# CANBUS_Pendant.net
KiCad netlist of a schematic drawn in Altium Designer
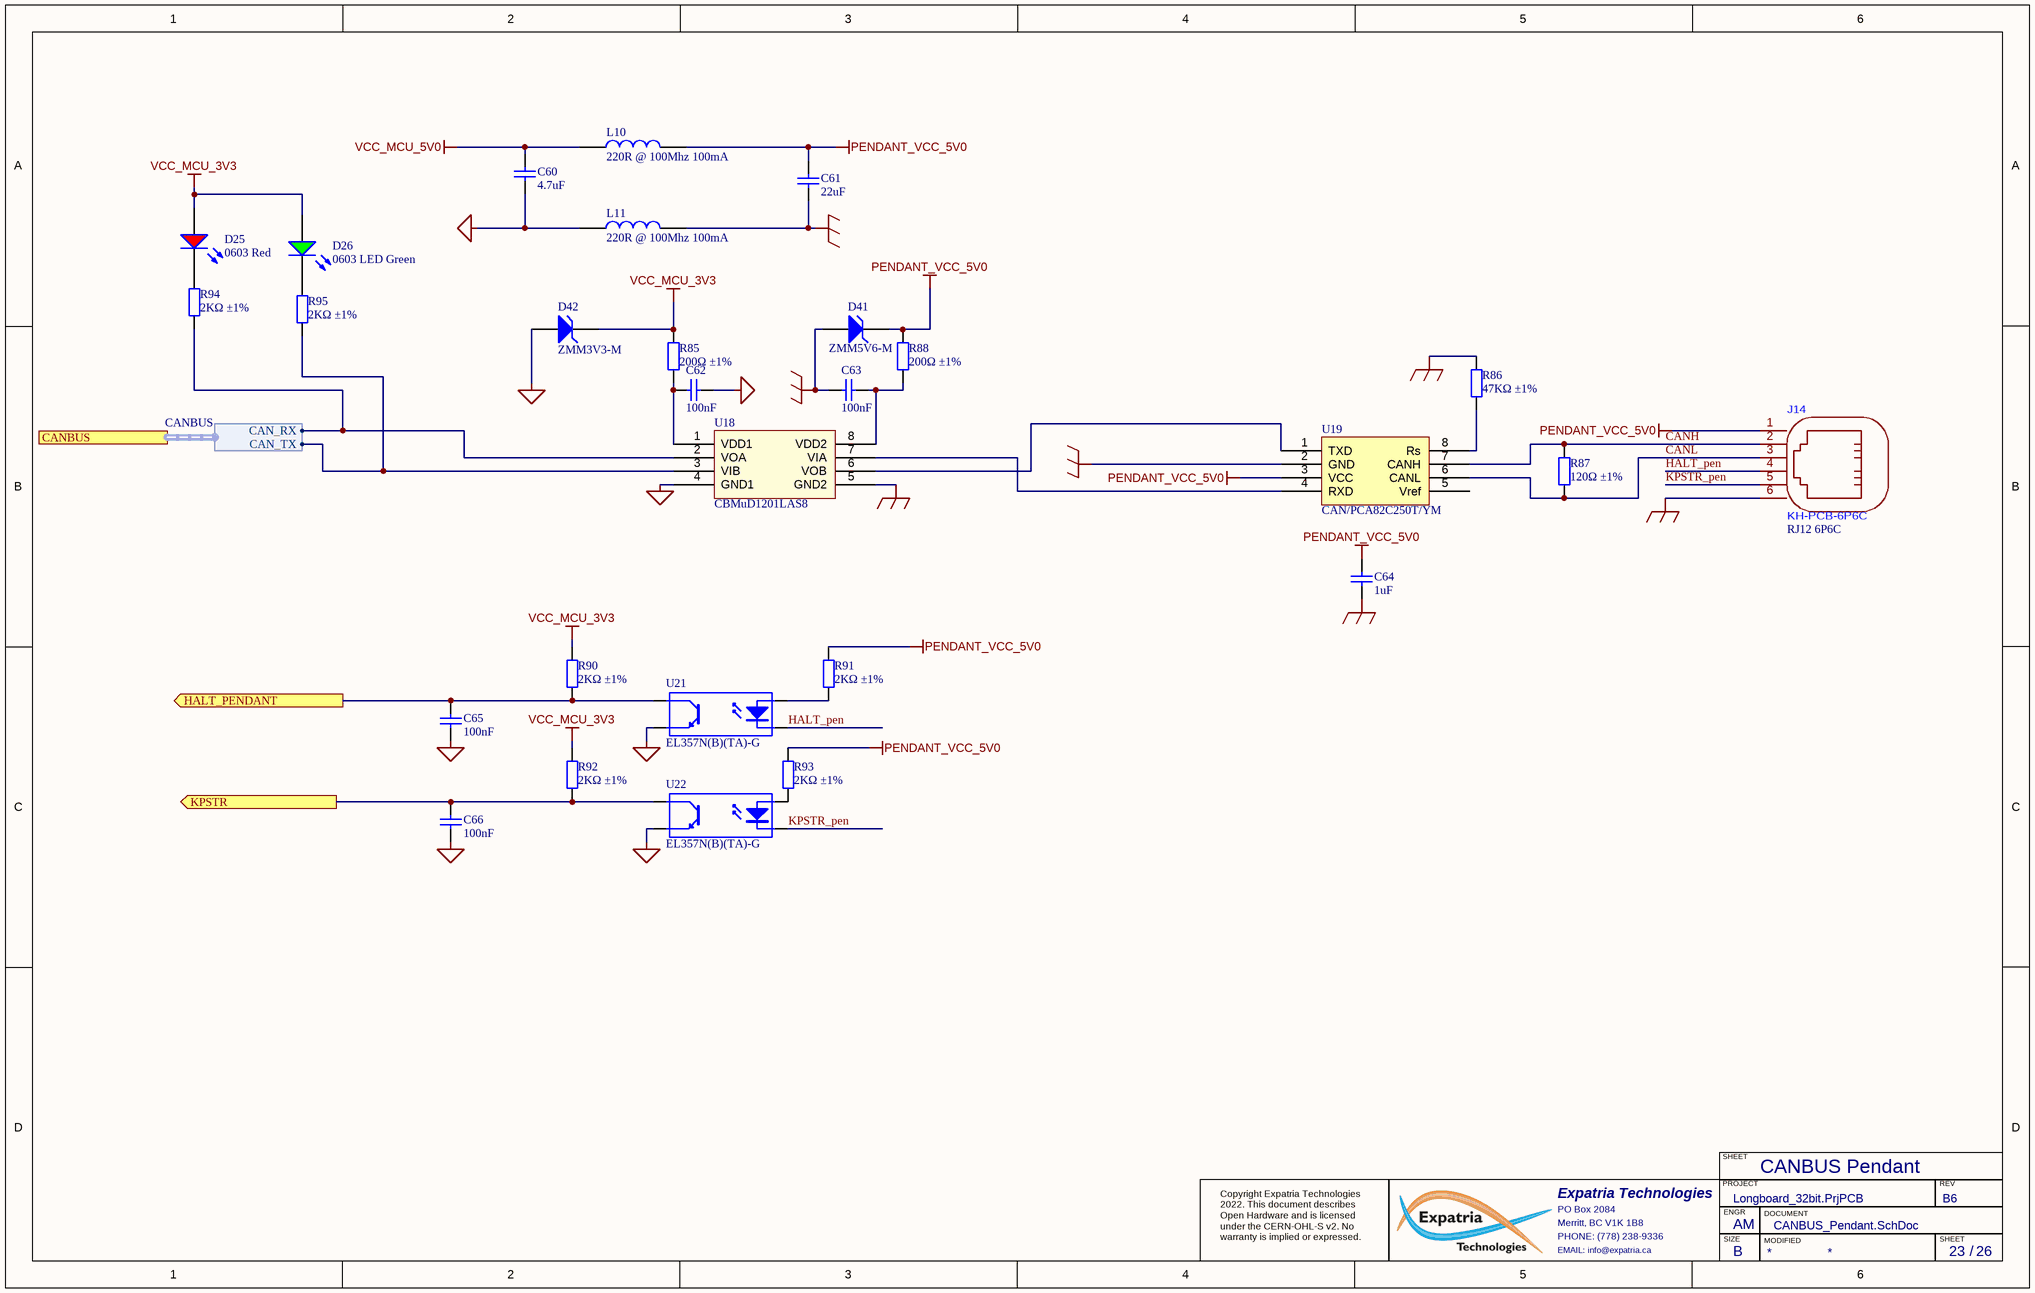
[diagram p0: CANBUS_Pendant.SchDoc]

(export (version "E")
  (design (tool "Eeschema 10.0.6"))
  (components
    (comp (ref "C60")
      (value "4.7uF")
      (footprint "0805_C")
      (description "Chip capacitors")
      (fields
        (field (name "MANUFACTURER") "Samsung Electro-Mechanics")
        (field (name "PARTNUMBER") "CL21A475KAQNNNE")
      )
      (libsource (lib "Cap") (part "0805 4.7uF (475) 10% 25V"))
    )
    (comp (ref "C61")
      (value "22uF")
      (footprint "0805_C")
      (description "25V 22uF X5R ±20% 0805 Multilayer Ceramic Capacitors MLCC - SMD/SMT ROHS")
      (fields (field (name "MANUFACTURER") "Samsung Electro-Mechanics") (field (name "TOLERANCE") "20%"))
      (libsource (lib "Sienci_Labs") (part "0805 22uF (226) 20% 25V"))
    )
    (comp (ref "C62")
      (value "100nF")
      (footprint "0402_C")
      (description "16V 100nF X7R ±10% 0402 Multilayer Ceramic Capacitors MLCC - SMD/SMT ROHS")
      (fields (field (name "MANUFACTURER") "Samsung Electro-Mechanics") (field (name "TOLERANCE") "10%"))
      (libsource (lib "Sienci_Labs") (part "0402 100nF (104) 10% 16V"))
    )
    (comp (ref "C63")
      (value "100nF")
      (footprint "0402_C")
      (description "16V 100nF X7R ±10% 0402 Multilayer Ceramic Capacitors MLCC - SMD/SMT ROHS")
      (fields (field (name "MANUFACTURER") "Samsung Electro-Mechanics") (field (name "TOLERANCE") "10%"))
      (libsource (lib "Sienci_Labs") (part "0402 100nF (104) 10% 16V"))
    )
    (comp (ref "C64")
      (value "1uF")
      (footprint "0603_C")
      (description "Chip capacitors")
      (fields
        (field (name "MANUFACTURER") "Samsung Electro-Mechanics")
        (field (name "MANUFACTURER PART NUMBER") "CL10A105KB8NNNC")
      )
      (libsource (lib "Cap") (part "0603 1uF (105) 10% 50V"))
    )
    (comp (ref "C65")
      (value "100nF")
      (footprint "0603_C")
      (description "50V 100nF X7R ±10% 0603 Multilayer Ceramic Capacitors MLCC - SMD/SMT ROHS")
      (fields
        (field (name "MANUFACTURER") "YAGEO")
        (field (name "MANUFACTURER PART NUMBER") "CC0603KRX7R9BB104")
      )
      (libsource (lib "Sienci_Labs") (part "0603 100nF (104) 10% 50V"))
    )
    (comp (ref "C66")
      (value "100nF")
      (footprint "0603_C")
      (description "50V 100nF X7R ±10% 0603 Multilayer Ceramic Capacitors MLCC - SMD/SMT ROHS")
      (fields
        (field (name "MANUFACTURER") "YAGEO")
        (field (name "MANUFACTURER PART NUMBER") "CC0603KRX7R9BB104")
      )
      (libsource (lib "Sienci_Labs") (part "0603 100nF (104) 10% 50V"))
    )
    (comp (ref "D25")
      (value "0603 Red")
      (footprint "0603_LED_S1")
      (fields
        (field (name "MANUFACTURER") "Everlight Elec")
        (field (name "MANUFACTURER PART NUMBER") "19-213SURC/S530-A3/TR8")
      )
      (libsource (lib "Sienci_Labs") (part "19-213SURC/S530-A3/TR8"))
    )
    (comp (ref "D26")
      (value "0603 LED Green")
      (footprint "0603_LED_S1 - GREEN")
      (fields
        (field (name "MANUFACTURER PART NUMBER") "19-217/GHC-YR1S2/3T")
        (field (name "MANUFACTURER") "Everlight Elec")
      )
      (libsource (lib "Sienci_Labs") (part "19-217/GHC-YR1S2/3T"))
    )
    (comp (ref "D41")
      (value "ZMM5V6-M")
      (footprint "LL-34")
      (description "Single 5.2V~6V 500mW 5.6V LL-34 Zener Diodes ROHS")
      (fields (field (name "MANUFACTURER") "ST(Semtech)"))
      (libsource (lib "Sienci_Labs") (part "LL-34 ZMM5V6-M"))
    )
    (comp (ref "D42")
      (value "ZMM3V3-M")
      (footprint "LL-34")
      (description "Single 3.1V~3.5V 500mW 3.3V LL-34 Zener Diodes ROHS")
      (fields (field (name "MANUFACTURER") "ST(Semtech)"))
      (libsource (lib "Sienci_Labs") (part "LL-34 ZMM3V3-M"))
    )
    (comp (ref "J14")
      (value "KH-PCB-6P6C")
      (footprint "RJ11-TH_DS1133-S60BPX")
      (fields
        (field (name "MANUFACTURER") "Shenzhen Kinghelm Elec")
        (field (name "ALTIUM_VALUE") "RJ12 6P6C")
      )
      (libsource (lib "Sienci_Labs") (part "KH-PCB-6P6C"))
    )
    (comp (ref "L10")
      (value "220R @ 100Mhz 100mA")
      (footprint "0402_L")
      (description "700mΩ ±25% 220Ω@100MHz 0402 Ferrite Beads ROHS")
      (fields
        (field (name "MANUFACTURER PART NUMBER") "CBG100505U221T")
        (field (name "MANUFACTURER") "FH (Guangdong Fenghua Advanced Tech)")
      )
      (libsource (lib "Sienci_Labs") (part "0402 220R@100Mhz 0.1A"))
    )
    (comp (ref "L11")
      (value "220R @ 100Mhz 100mA")
      (footprint "0402_L")
      (description "700mΩ ±25% 220Ω@100MHz 0402 Ferrite Beads ROHS")
      (fields
        (field (name "MANUFACTURER PART NUMBER") "CBG100505U221T")
        (field (name "MANUFACTURER") "FH (Guangdong Fenghua Advanced Tech)")
      )
      (libsource (lib "Sienci_Labs") (part "0402 220R@100Mhz 0.1A"))
    )
    (comp (ref "R85")
      (value "200Ω ±1%")
      (footprint "0402_R")
      (description "Chip resistor")
      (fields (field (name "MANUFACTURER") "Uniroyal Elec") (field (name "PARTNUMBER") "0402WGF2000TCE"))
      (libsource (lib "RES") (part "0402 200R (2000) 1%"))
    )
    (comp (ref "R86")
      (value "47KΩ ±1%")
      (footprint "0402_R")
      (description "Chip resistor")
      (fields (field (name "MANUFACTURER") "Uniroyal Elec") (field (name "PARTNUMBER") "0402WGF4702TCE"))
      (libsource (lib "RES") (part "0402 47K (4702) 1%"))
    )
    (comp (ref "R87")
      (value "120Ω ±1%")
      (footprint "0805_R")
      (description "Chip resistor")
      (fields
        (field (name "MANUFACTURER") "Uniroyal Elec")
        (field (name "MANUFACTURER PART NUMBER") "0805W8F1200T5E")
      )
      (libsource (lib "RES") (part "0805 120R (1200) 1%"))
    )
    (comp (ref "R88")
      (value "200Ω ±1%")
      (footprint "0402_R")
      (description "Chip resistor")
      (fields (field (name "MANUFACTURER") "Uniroyal Elec") (field (name "PARTNUMBER") "0402WGF2000TCE"))
      (libsource (lib "RES") (part "0402 200R (2000) 1%"))
    )
    (comp (ref "R90")
      (value "2KΩ ±1%")
      (footprint "0402_R")
      (description "Chip resistor")
      (fields (field (name "MANUFACTURER") "Uniroyal Elec") (field (name "PARTNUMBER") "0402WGF2001TCE"))
      (libsource (lib "RES") (part "0402 2K (2001) 1%"))
    )
    (comp (ref "R91")
      (value "2KΩ ±1%")
      (footprint "0402_R")
      (description "Chip resistor")
      (fields (field (name "MANUFACTURER") "Uniroyal Elec") (field (name "PARTNUMBER") "0402WGF2001TCE"))
      (libsource (lib "RES") (part "0402 2K (2001) 1%"))
    )
    (comp (ref "R92")
      (value "2KΩ ±1%")
      (footprint "0402_R")
      (description "Chip resistor")
      (fields (field (name "MANUFACTURER") "Uniroyal Elec") (field (name "PARTNUMBER") "0402WGF2001TCE"))
      (libsource (lib "RES") (part "0402 2K (2001) 1%"))
    )
    (comp (ref "R93")
      (value "2KΩ ±1%")
      (footprint "0402_R")
      (description "Chip resistor")
      (fields (field (name "MANUFACTURER") "Uniroyal Elec") (field (name "PARTNUMBER") "0402WGF2001TCE"))
      (libsource (lib "RES") (part "0402 2K (2001) 1%"))
    )
    (comp (ref "R94")
      (value "2KΩ ±1%")
      (footprint "0402_R")
      (description "Chip resistor")
      (fields (field (name "MANUFACTURER") "Uniroyal Elec") (field (name "PARTNUMBER") "0402WGF2001TCE"))
      (libsource (lib "RES") (part "0402 2K (2001) 1%"))
    )
    (comp (ref "R95")
      (value "2KΩ ±1%")
      (footprint "0402_R")
      (description "Chip resistor")
      (fields (field (name "MANUFACTURER") "Uniroyal Elec") (field (name "PARTNUMBER") "0402WGF2001TCE"))
      (libsource (lib "RES") (part "0402 2K (2001) 1%"))
    )
    (comp (ref "U18")
      (value "CBMuD1201LAS8")
      (footprint "SOIC-8_150mil")
      (description "Dual Channel Isolator")
      (fields (field (name "MANUFACTURER") "Corebai Microelectronics"))
      (libsource (lib "Sienci_Labs") (part "CBMuD1201LAS8"))
    )
    (comp (ref "U19")
      (value "CAN/PCA82C250T/YM")
      (footprint "SOIC-8_150mil")
      (description "CAN")
      (fields
        (field (name "MANUFACTURER PART NUMBER") "PCA82C250T/YM,118")
        (field (name "MANUFACTURER") "NXP Semicon")
      )
      (libsource (lib "IC") (part "CAN/PCA82C250T/YM_[C7439]"))
    )
    (comp (ref "U21")
      (value "EL357N(B)(TA)-G")
      (footprint "Miscellaneous Devices LC:SOP-4_P2.54")
      (description "80V 3750V 50mA 0.1V@1mA,20mA 1 6V 1.2V DC SOP-4-2.54mm Optocouplers - Phototransistor Output ROHS")
      (fields (field (name "MANUFACTURER") "Everlight Elec"))
      (libsource (lib "IC") (part "EL357N(B)(TA)-G_[C6649]"))
    )
    (comp (ref "U22")
      (value "EL357N(B)(TA)-G")
      (footprint "Miscellaneous Devices LC:SOP-4_P2.54")
      (description "80V 3750V 50mA 0.1V@1mA,20mA 1 6V 1.2V DC SOP-4-2.54mm Optocouplers - Phototransistor Output ROHS")
      (fields (field (name "MANUFACTURER") "Everlight Elec"))
      (libsource (lib "IC") (part "EL357N(B)(TA)-G_[C6649]"))
    )
  )
  (nets
    (net (code "2") (name "/CANH") (class "Default")
      (node (ref "J14") (pin "2") (pinfunction "VDD_2") (pintype "passive"))
      (node (ref "R87") (pin "2") (pinfunction "2_2") (pintype "passive"))
      (node (ref "U19") (pin "7") (pinfunction "CANH_7") (pintype "passive"))
    )
    (net (code "3") (name "/CANL") (class "Default")
      (node (ref "J14") (pin "3") (pinfunction "VSS_3") (pintype "passive"))
      (node (ref "R87") (pin "1") (pinfunction "1_1") (pintype "passive"))
      (node (ref "U19") (pin "6") (pinfunction "CANL_6") (pintype "passive"))
    )
    (net (code "4") (name "/HALT_PENDANT") (class "Default")
      (node (ref "C65") (pin "2") (pinfunction "2_2") (pintype "passive"))
      (node (ref "R90") (pin "1") (pinfunction "1_1") (pintype "passive"))
      (node (ref "U21") (pin "4") (pinfunction "C_4") (pintype "passive"))
    )
    (net (code "5") (name "/HALT_pen") (class "Default")
      (node (ref "J14") (pin "4") (pinfunction "PGD_4") (pintype "passive"))
      (node (ref "U21") (pin "2") (pinfunction "K_2") (pintype "passive"))
    )
    (net (code "6") (name "/KPSTR") (class "Default")
      (node (ref "C66") (pin "2") (pinfunction "2_2") (pintype "passive"))
      (node (ref "R92") (pin "1") (pinfunction "1_1") (pintype "passive"))
      (node (ref "U22") (pin "4") (pinfunction "C_4") (pintype "passive"))
    )
    (net (code "7") (name "/KPSTR_pen") (class "Default")
      (node (ref "J14") (pin "5") (pinfunction "PGC_5") (pintype "passive"))
      (node (ref "U22") (pin "2") (pinfunction "K_2") (pintype "passive"))
    )
    (net (code "9") (name "MCU_GND") (class "Default")
      (node (ref "C60") (pin "1") (pinfunction "1_1") (pintype "passive"))
      (node (ref "C62") (pin "2") (pinfunction "2_2") (pintype "passive"))
      (node (ref "C65") (pin "1") (pinfunction "1_1") (pintype "passive"))
      (node (ref "C66") (pin "1") (pinfunction "1_1") (pintype "passive"))
      (node (ref "D42") (pin "1") (pinfunction "A_1") (pintype "passive"))
      (node (ref "L11") (pin "1") (pinfunction "1_1") (pintype "passive"))
      (node (ref "U18") (pin "4") (pinfunction "GND1_4") (pintype "passive"))
      (node (ref "U21") (pin "3") (pinfunction "E_3") (pintype "passive"))
      (node (ref "U22") (pin "3") (pinfunction "E_3") (pintype "passive"))
    )
    (net (code "10") (name "Net-(D25-PadK)") (class "Default")
      (node (ref "D25") (pin "K") (pinfunction "K_K") (pintype "passive"))
      (node (ref "R94") (pin "2") (pinfunction "2_2") (pintype "passive"))
    )
    (net (code "11") (name "Net-(D26-PadK)") (class "Default")
      (node (ref "D26") (pin "K") (pinfunction "K_K") (pintype "passive"))
      (node (ref "R95") (pin "2") (pinfunction "2_2") (pintype "passive"))
    )
    (net (code "12") (name "Net-(U18-VDD1)") (class "Default")
      (node (ref "C62") (pin "1") (pinfunction "1_1") (pintype "passive"))
      (node (ref "R85") (pin "1") (pinfunction "1_1") (pintype "passive"))
      (node (ref "U18") (pin "1") (pinfunction "VDD1_1") (pintype "passive"))
    )
    (net (code "13") (name "Net-(U18-VDD2)") (class "Default")
      (node (ref "C63") (pin "2") (pinfunction "2_2") (pintype "passive"))
      (node (ref "R88") (pin "1") (pinfunction "1_1") (pintype "passive"))
      (node (ref "U18") (pin "8") (pinfunction "VDD2_8") (pintype "passive"))
    )
    (net (code "14") (name "Net-(U18-VIA)") (class "Default")
      (node (ref "U18") (pin "7") (pinfunction "VIA_7") (pintype "passive"))
      (node (ref "U19") (pin "4") (pinfunction "RXD_4") (pintype "passive"))
    )
    (net (code "15") (name "Net-(U18-VIB)") (class "Default")
      (node (ref "R95") (pin "1") (pinfunction "1_1") (pintype "passive"))
      (node (ref "U18") (pin "3") (pinfunction "VIB_3") (pintype "passive"))
    )
    (net (code "16") (name "Net-(U18-VOA)") (class "Default")
      (node (ref "R94") (pin "1") (pinfunction "1_1") (pintype "passive"))
      (node (ref "U18") (pin "2") (pinfunction "VOA_2") (pintype "passive"))
    )
    (net (code "17") (name "Net-(U18-VOB)") (class "Default")
      (node (ref "U18") (pin "6") (pinfunction "VOB_6") (pintype "passive"))
      (node (ref "U19") (pin "1") (pinfunction "TXD_1") (pintype "passive"))
    )
    (net (code "18") (name "Net-(U19-Rs)") (class "Default")
      (node (ref "R86") (pin "1") (pinfunction "1_1") (pintype "passive"))
      (node (ref "U19") (pin "8") (pinfunction "Rs_8") (pintype "passive"))
    )
    (net (code "19") (name "Net-(U21-A)") (class "Default")
      (node (ref "R91") (pin "1") (pinfunction "1_1") (pintype "passive"))
      (node (ref "U21") (pin "1") (pinfunction "A_1") (pintype "passive"))
    )
    (net (code "20") (name "Net-(U22-A)") (class "Default")
      (node (ref "R93") (pin "1") (pinfunction "1_1") (pintype "passive"))
      (node (ref "U22") (pin "1") (pinfunction "A_1") (pintype "passive"))
    )
    (net (code "21") (name "PENDANT_VCC_5V0") (class "Default")
      (node (ref "C61") (pin "2") (pinfunction "2_2") (pintype "passive"))
      (node (ref "C64") (pin "2") (pinfunction "2_2") (pintype "passive"))
      (node (ref "D41") (pin "2") (pinfunction "K_2") (pintype "passive"))
      (node (ref "J14") (pin "1") (pinfunction "MCLR_1") (pintype "passive"))
      (node (ref "L10") (pin "2") (pinfunction "2_2") (pintype "passive"))
      (node (ref "R88") (pin "2") (pinfunction "2_2") (pintype "passive"))
      (node (ref "R91") (pin "2") (pinfunction "2_2") (pintype "passive"))
      (node (ref "R93") (pin "2") (pinfunction "2_2") (pintype "passive"))
      (node (ref "U19") (pin "3") (pinfunction "VCC_3") (pintype "passive"))
    )
    (net (code "22") (name "PEND_GND") (class "Default")
      (node (ref "C61") (pin "1") (pinfunction "1_1") (pintype "passive"))
      (node (ref "C63") (pin "1") (pinfunction "1_1") (pintype "passive"))
      (node (ref "C64") (pin "1") (pinfunction "1_1") (pintype "passive"))
      (node (ref "D41") (pin "1") (pinfunction "A_1") (pintype "passive"))
      (node (ref "J14") (pin "6") (pinfunction "NC_6") (pintype "passive"))
      (node (ref "L11") (pin "2") (pinfunction "2_2") (pintype "passive"))
      (node (ref "R86") (pin "2") (pinfunction "2_2") (pintype "passive"))
      (node (ref "U18") (pin "5") (pinfunction "GND2_5") (pintype "passive"))
      (node (ref "U19") (pin "2") (pinfunction "GND_2") (pintype "passive"))
    )
    (net (code "23") (name "VCC_MCU_3V3") (class "Default")
      (node (ref "D25") (pin "A") (pinfunction "A_A") (pintype "passive"))
      (node (ref "D26") (pin "A") (pinfunction "A_A") (pintype "passive"))
      (node (ref "D42") (pin "2") (pinfunction "K_2") (pintype "passive"))
      (node (ref "R85") (pin "2") (pinfunction "2_2") (pintype "passive"))
      (node (ref "R90") (pin "2") (pinfunction "2_2") (pintype "passive"))
      (node (ref "R92") (pin "2") (pinfunction "2_2") (pintype "passive"))
    )
    (net (code "24") (name "VCC_MCU_5V0") (class "Default")
      (node (ref "C60") (pin "2") (pinfunction "2_2") (pintype "passive"))
      (node (ref "L10") (pin "1") (pinfunction "1_1") (pintype "passive"))
    )
    (net (code "25") (name "unconnected-(U19-Vref-Pad5)") (class "Default")
      (node (ref "U19") (pin "5") (pinfunction "Vref_5") (pintype "passive"))
    )
  )
)
